# lat_stm_zybo.net
KiCad netlist of a schematic drawn in EAGLE
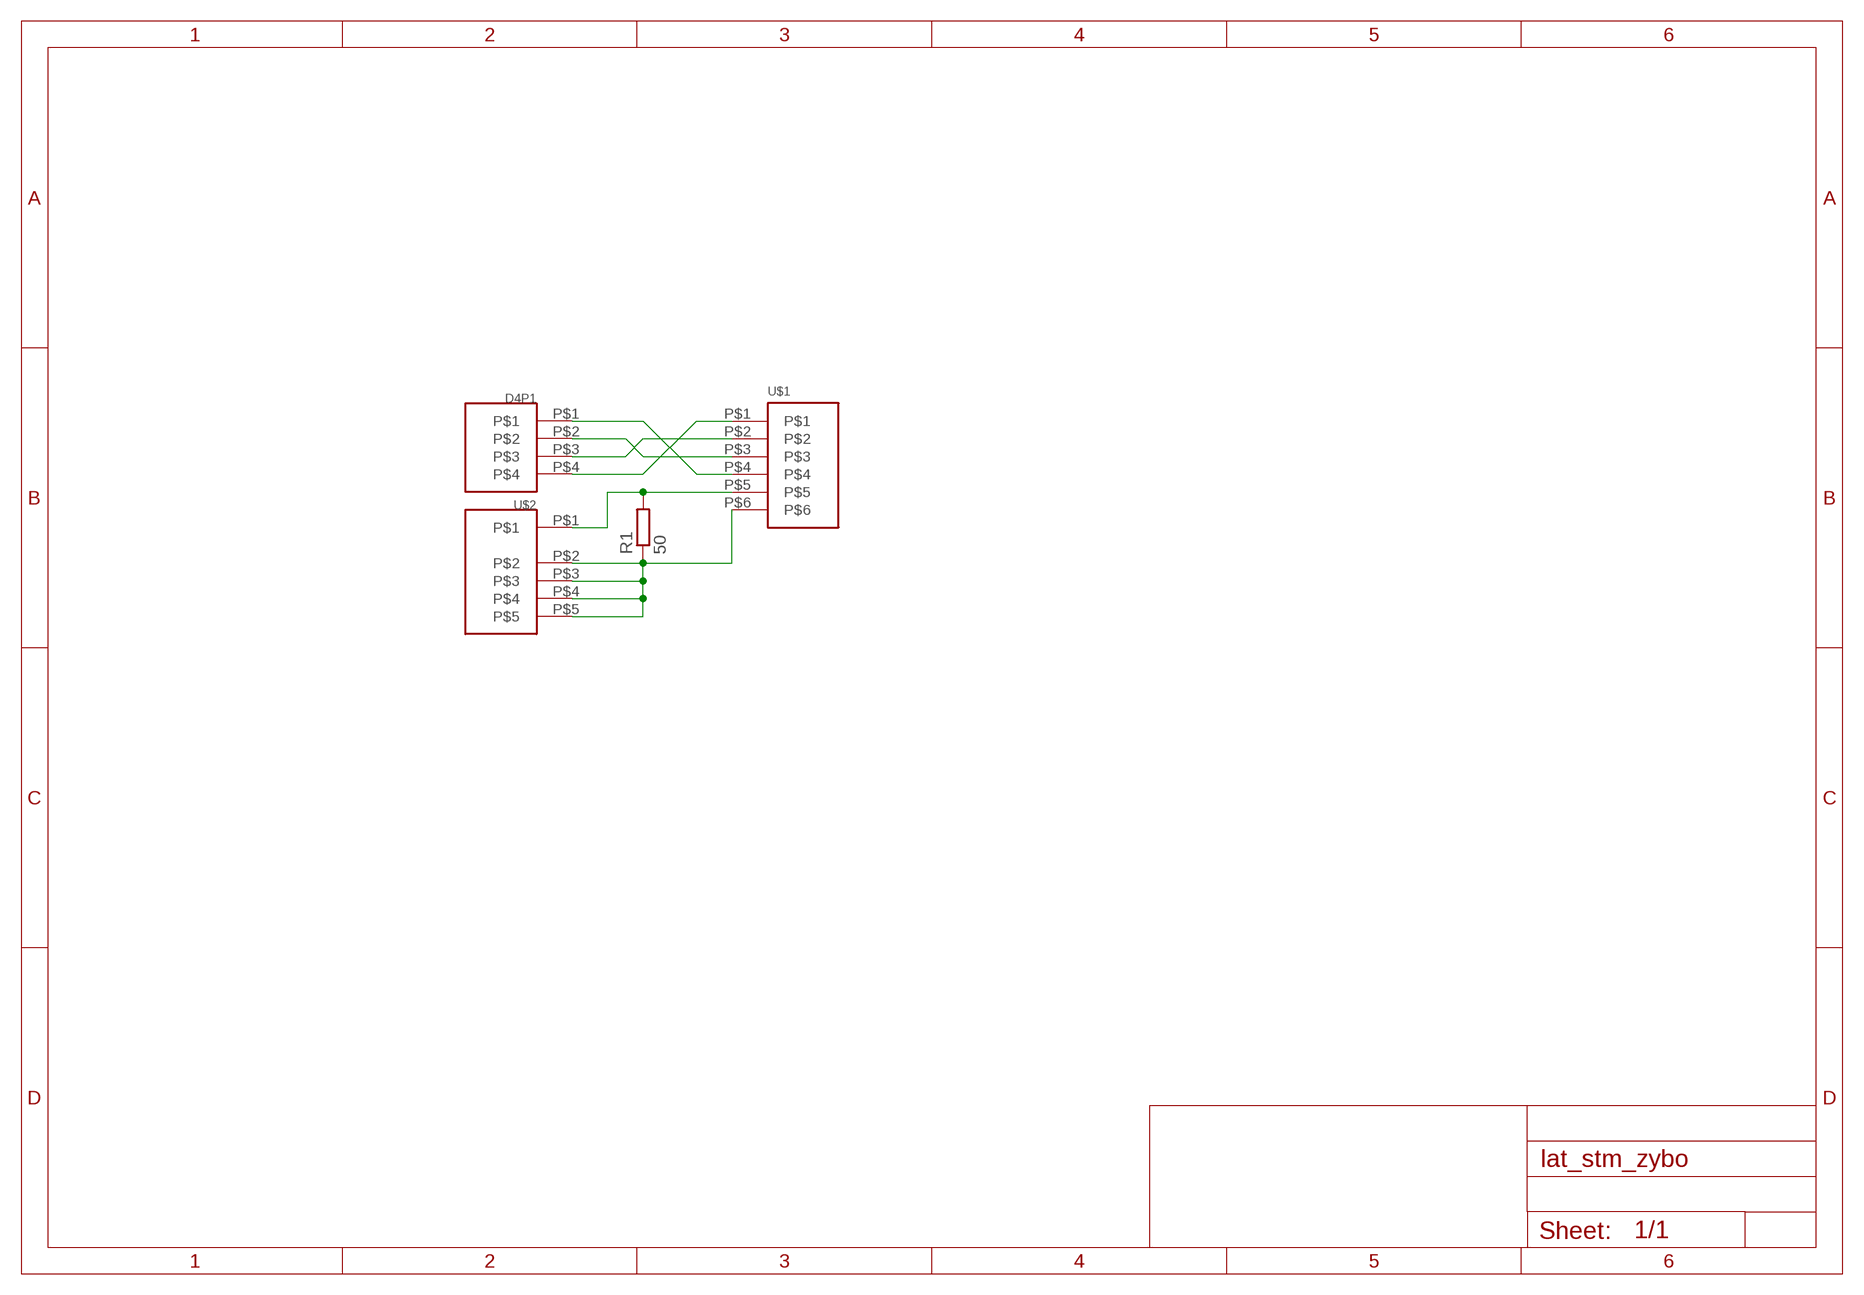
[diagram p0: schematic, sheet 1]

(export (version "E")
  (design (tool "Eeschema 10.0.6"))
  (components
    (comp (ref "D4P1")
      (value "DF1E-4P")
      (footprint "eagle-import:DF1E-4P")
      (libsource (lib "eagle-import") (part "DF1E-4P"))
    )
    (comp (ref "R1")
      (value "50")
      (footprint "eagle-import:0204_7")
      (libsource (lib "eagle-import") (part "R-EU_0204/7"))
    )
    (comp (ref "U$1")
      (value "DF1E-6P")
      (footprint "eagle-import:DF1E-6P")
      (libsource (lib "eagle-import") (part "DF1E-6P"))
    )
    (comp (ref "U$2")
      (value "546-4049")
      (footprint "eagle-import:546-4049")
      (libsource (lib "eagle-import") (part "546-4049"))
    )
  )
  (nets
    (net (code "1") (name "Net-(D4P1-PadP$1)") (class "Default")
      (node (ref "D4P1") (pin "P$1") (pinfunction "P$1_P$1") (pintype "bidirectional"))
      (node (ref "U$1") (pin "P$4") (pinfunction "P$4_P$4") (pintype "bidirectional"))
    )
    (net (code "2") (name "Net-(D4P1-PadP$2)") (class "Default")
      (node (ref "D4P1") (pin "P$2") (pinfunction "P$2_P$2") (pintype "bidirectional"))
      (node (ref "U$1") (pin "P$3") (pinfunction "P$3_P$3") (pintype "bidirectional"))
    )
    (net (code "3") (name "Net-(D4P1-PadP$3)") (class "Default")
      (node (ref "D4P1") (pin "P$3") (pinfunction "P$3_P$3") (pintype "bidirectional"))
      (node (ref "U$1") (pin "P$2") (pinfunction "P$2_P$2") (pintype "bidirectional"))
    )
    (net (code "4") (name "Net-(D4P1-PadP$4)") (class "Default")
      (node (ref "D4P1") (pin "P$4") (pinfunction "P$4_P$4") (pintype "bidirectional"))
      (node (ref "U$1") (pin "P$1") (pinfunction "P$1_P$1") (pintype "bidirectional"))
    )
    (net (code "5") (name "Net-(R1-Pad1)") (class "Default")
      (node (ref "R1") (pin "1") (pinfunction "1_1") (pintype "passive"))
      (node (ref "U$1") (pin "P$6") (pinfunction "P$6_P$6") (pintype "bidirectional"))
      (node (ref "U$2") (pin "P$2") (pinfunction "P$2_P$2") (pintype "bidirectional"))
      (node (ref "U$2") (pin "P$3") (pinfunction "P$3_P$3") (pintype "bidirectional"))
      (node (ref "U$2") (pin "P$4") (pinfunction "P$4_P$4") (pintype "bidirectional"))
      (node (ref "U$2") (pin "P$5") (pinfunction "P$5_P$5") (pintype "bidirectional"))
    )
    (net (code "6") (name "Net-(R1-Pad2)") (class "Default")
      (node (ref "R1") (pin "2") (pinfunction "2_2") (pintype "passive"))
      (node (ref "U$1") (pin "P$5") (pinfunction "P$5_P$5") (pintype "bidirectional"))
      (node (ref "U$2") (pin "P$1") (pinfunction "P$1_P$1") (pintype "bidirectional"))
    )
  )
)
